# Sheet_V_3.net
KiCad netlist of a schematic drawn in Altium Designer
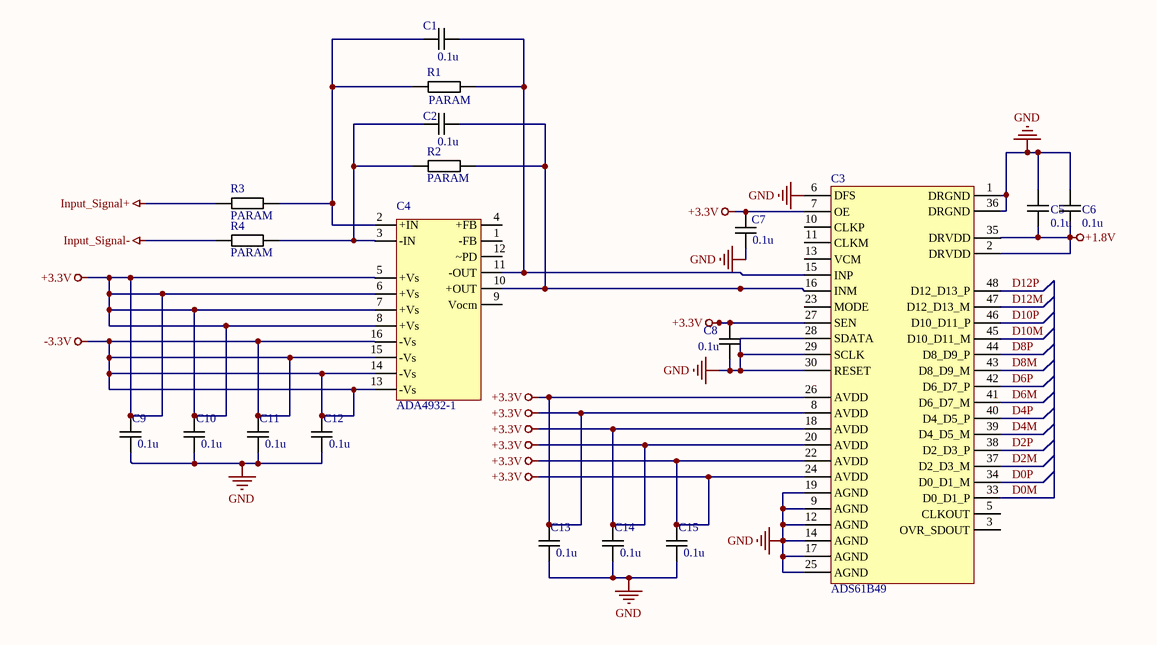
[diagram p0: Sheet_V№3.SchDoc]

(export (version "E")
  (design (tool "Eeschema 10.0.6"))
  (components
    (comp (ref "C1")
      (value "0.1u")
      (footprint "Capacitor")
      (libsource (lib "Schematic_Library_V№6") (part "Capacitor"))
    )
    (comp (ref "C2")
      (value "0.1u")
      (footprint "Capacitor")
      (libsource (lib "Schematic_Library_V№6") (part "Capacitor"))
    )
    (comp (ref "C3")
      (value "ADS61B49")
      (footprint "ADS61B49")
      (libsource (lib "Schematic_library_V№3") (part "ADS61B49"))
    )
    (comp (ref "C4")
      (value "ADA4932-1")
      (footprint "PCB_Library_V№6:CP-16-2")
      (libsource (lib "Schematic_Library_V№6") (part "ADA4932-1"))
    )
    (comp (ref "C5")
      (value "0.1u")
      (footprint "Capacitor")
      (libsource (lib "Schematic_library_V№3") (part "Capacitor"))
    )
    (comp (ref "C6")
      (value "0.1u")
      (footprint "Capacitor")
      (libsource (lib "Schematic_library_V№3") (part "Capacitor"))
    )
    (comp (ref "C7")
      (value "0.1u")
      (footprint "Capacitor")
      (libsource (lib "Schematic_Library_V№6") (part "Capacitor"))
    )
    (comp (ref "C8")
      (value "0.1u")
      (footprint "Capacitor")
      (libsource (lib "Schematic_library_V№3") (part "Capacitor"))
    )
    (comp (ref "C9")
      (value "0.1u")
      (footprint "Capacitor")
      (libsource (lib "Schematic_Library_V№6") (part "Capacitor"))
    )
    (comp (ref "C10")
      (value "0.1u")
      (footprint "Capacitor")
      (libsource (lib "Schematic_Library_V№6") (part "Capacitor"))
    )
    (comp (ref "C11")
      (value "0.1u")
      (footprint "Capacitor")
      (libsource (lib "Schematic_Library_V№6") (part "Capacitor"))
    )
    (comp (ref "C12")
      (value "0.1u")
      (footprint "Capacitor")
      (libsource (lib "Schematic_Library_V№6") (part "Capacitor"))
    )
    (comp (ref "C13")
      (value "0.1u")
      (footprint "Capacitor")
      (libsource (lib "Schematic_Library_V№6") (part "Capacitor"))
    )
    (comp (ref "C14")
      (value "0.1u")
      (footprint "Capacitor")
      (libsource (lib "Schematic_Library_V№6") (part "Capacitor"))
    )
    (comp (ref "C15")
      (value "0.1u")
      (footprint "Capacitor")
      (libsource (lib "Schematic_Library_V№6") (part "Capacitor"))
    )
    (comp (ref "R1")
      (value "PARAM")
      (footprint "Resistor")
      (libsource (lib "Schematic_Library_V№6") (part "Resistor"))
    )
    (comp (ref "R2")
      (value "PARAM")
      (footprint "Resistor")
      (libsource (lib "Schematic_Library_V№6") (part "Resistor"))
    )
    (comp (ref "R3")
      (value "PARAM")
      (footprint "Resistor")
      (libsource (lib "Schematic_Library_V№6") (part "Resistor"))
    )
    (comp (ref "R4")
      (value "PARAM")
      (footprint "Resistor")
      (libsource (lib "Schematic_Library_V№6") (part "Resistor"))
    )
  )
  (nets
    (net (code "1") (name "+1.8V") (class "Default")
      (node (ref "C3") (pin "2") (pinfunction "DRVDD_2") (pintype "power_in"))
      (node (ref "C3") (pin "35") (pinfunction "DRVDD_35") (pintype "power_in"))
      (node (ref "C5") (pin "2") (pinfunction "2_2") (pintype "passive"))
      (node (ref "C6") (pin "2") (pinfunction "2_2") (pintype "passive"))
    )
    (net (code "2") (name "+3.3V") (class "Default")
      (node (ref "C10") (pin "2") (pinfunction "2_2") (pintype "passive"))
      (node (ref "C13") (pin "2") (pinfunction "2_2") (pintype "passive"))
      (node (ref "C14") (pin "2") (pinfunction "2_2") (pintype "passive"))
      (node (ref "C15") (pin "2") (pinfunction "2_2") (pintype "passive"))
      (node (ref "C3") (pin "18") (pinfunction "AVDD_18") (pintype "power_in"))
      (node (ref "C3") (pin "20") (pinfunction "AVDD_20") (pintype "power_in"))
      (node (ref "C3") (pin "22") (pinfunction "AVDD_22") (pintype "power_in"))
      (node (ref "C3") (pin "24") (pinfunction "AVDD_24") (pintype "power_in"))
      (node (ref "C3") (pin "26") (pinfunction "AVDD_26") (pintype "power_in"))
      (node (ref "C3") (pin "27") (pinfunction "SEN_27") (pintype "passive"))
      (node (ref "C3") (pin "7") (pinfunction "OE_7") (pintype "passive"))
      (node (ref "C3") (pin "8") (pinfunction "AVDD_8") (pintype "power_in"))
      (node (ref "C4") (pin "5") (pinfunction "+Vs_5") (pintype "passive"))
      (node (ref "C4") (pin "6") (pinfunction "+Vs_6") (pintype "passive"))
      (node (ref "C4") (pin "7") (pinfunction "+Vs_7") (pintype "passive"))
      (node (ref "C4") (pin "8") (pinfunction "+Vs_8") (pintype "passive"))
      (node (ref "C7") (pin "2") (pinfunction "2_2") (pintype "passive"))
      (node (ref "C8") (pin "2") (pinfunction "2_2") (pintype "passive"))
      (node (ref "C9") (pin "2") (pinfunction "2_2") (pintype "passive"))
    )
    (net (code "3") (name "-3.3V") (class "Default")
      (node (ref "C11") (pin "2") (pinfunction "2_2") (pintype "passive"))
      (node (ref "C12") (pin "2") (pinfunction "2_2") (pintype "passive"))
      (node (ref "C4") (pin "13") (pinfunction "-Vs_13") (pintype "passive"))
      (node (ref "C4") (pin "14") (pinfunction "-Vs_14") (pintype "passive"))
      (node (ref "C4") (pin "15") (pinfunction "-Vs_15") (pintype "passive"))
      (node (ref "C4") (pin "16") (pinfunction "-Vs_16") (pintype "passive"))
    )
    (net (code "4") (name "/D0M") (class "Default")
      (node (ref "C3") (pin "33") (pinfunction "D0_D1_P_33") (pintype "passive"))
    )
    (net (code "5") (name "/D0P") (class "Default")
      (node (ref "C3") (pin "34") (pinfunction "D0_D1_M_34") (pintype "passive"))
    )
    (net (code "6") (name "/D2M") (class "Default")
      (node (ref "C3") (pin "37") (pinfunction "D2_D3_M_37") (pintype "passive"))
    )
    (net (code "7") (name "/D2P") (class "Default")
      (node (ref "C3") (pin "38") (pinfunction "D2_D3_P_38") (pintype "passive"))
    )
    (net (code "8") (name "/D4M") (class "Default")
      (node (ref "C3") (pin "39") (pinfunction "D4_D5_M_39") (pintype "passive"))
    )
    (net (code "9") (name "/D4P") (class "Default")
      (node (ref "C3") (pin "40") (pinfunction "D4_D5_P_40") (pintype "passive"))
    )
    (net (code "10") (name "/D6M") (class "Default")
      (node (ref "C3") (pin "41") (pinfunction "D6_D7_M_41") (pintype "passive"))
    )
    (net (code "11") (name "/D6P") (class "Default")
      (node (ref "C3") (pin "42") (pinfunction "D6_D7_P_42") (pintype "passive"))
    )
    (net (code "12") (name "/D8M") (class "Default")
      (node (ref "C3") (pin "43") (pinfunction "D8_D9_M_43") (pintype "passive"))
    )
    (net (code "13") (name "/D8P") (class "Default")
      (node (ref "C3") (pin "44") (pinfunction "D8_D9_P_44") (pintype "passive"))
    )
    (net (code "14") (name "/D10M") (class "Default")
      (node (ref "C3") (pin "45") (pinfunction "D10_D11_M_45") (pintype "passive"))
    )
    (net (code "15") (name "/D10P") (class "Default")
      (node (ref "C3") (pin "46") (pinfunction "D10_D11_P_46") (pintype "passive"))
    )
    (net (code "16") (name "/D12M") (class "Default")
      (node (ref "C3") (pin "47") (pinfunction "D12_D13_M_47") (pintype "passive"))
    )
    (net (code "17") (name "/D12P") (class "Default")
      (node (ref "C3") (pin "48") (pinfunction "D12_D13_P_48") (pintype "passive"))
    )
    (net (code "18") (name "GND") (class "Default")
      (node (ref "C10") (pin "1") (pinfunction "1_1") (pintype "passive"))
      (node (ref "C11") (pin "1") (pinfunction "1_1") (pintype "passive"))
      (node (ref "C12") (pin "1") (pinfunction "1_1") (pintype "passive"))
      (node (ref "C13") (pin "1") (pinfunction "1_1") (pintype "passive"))
      (node (ref "C14") (pin "1") (pinfunction "1_1") (pintype "passive"))
      (node (ref "C15") (pin "1") (pinfunction "1_1") (pintype "passive"))
      (node (ref "C3") (pin "1") (pinfunction "DRGND_1") (pintype "power_in"))
      (node (ref "C3") (pin "12") (pinfunction "AGND_12") (pintype "power_in"))
      (node (ref "C3") (pin "14") (pinfunction "AGND_14") (pintype "power_in"))
      (node (ref "C3") (pin "17") (pinfunction "AGND_17") (pintype "power_in"))
      (node (ref "C3") (pin "19") (pinfunction "AGND_19") (pintype "power_in"))
      (node (ref "C3") (pin "25") (pinfunction "AGND_25") (pintype "power_in"))
      (node (ref "C3") (pin "28") (pinfunction "SDATA_28") (pintype "passive"))
      (node (ref "C3") (pin "29") (pinfunction "SCLK_29") (pintype "passive"))
      (node (ref "C3") (pin "30") (pinfunction "RESET_30") (pintype "passive"))
      (node (ref "C3") (pin "36") (pinfunction "DRGND_36") (pintype "power_in"))
      (node (ref "C3") (pin "6") (pinfunction "DFS_6") (pintype "passive"))
      (node (ref "C3") (pin "9") (pinfunction "AGND_9") (pintype "power_in"))
      (node (ref "C5") (pin "1") (pinfunction "1_1") (pintype "passive"))
      (node (ref "C6") (pin "1") (pinfunction "1_1") (pintype "passive"))
      (node (ref "C7") (pin "1") (pinfunction "1_1") (pintype "passive"))
      (node (ref "C8") (pin "1") (pinfunction "1_1") (pintype "passive"))
      (node (ref "C9") (pin "1") (pinfunction "1_1") (pintype "passive"))
    )
    (net (code "19") (name "Input_Signal+") (class "Default")
      (node (ref "R3") (pin "1") (pinfunction "1_1") (pintype "passive"))
    )
    (net (code "20") (name "Input_Signal-") (class "Default")
      (node (ref "R4") (pin "1") (pinfunction "1_1") (pintype "passive"))
    )
    (net (code "21") (name "Net-(C3-INM)") (class "Default")
      (node (ref "C2") (pin "2") (pinfunction "2_2") (pintype "passive"))
      (node (ref "C3") (pin "16") (pinfunction "INM_16") (pintype "passive"))
      (node (ref "C4") (pin "10") (pinfunction "+OUT_10") (pintype "passive"))
      (node (ref "R2") (pin "2") (pinfunction "2_2") (pintype "passive"))
    )
    (net (code "22") (name "Net-(C3-INP)") (class "Default")
      (node (ref "C1") (pin "1") (pinfunction "1_1") (pintype "passive"))
      (node (ref "C3") (pin "15") (pinfunction "INP_15") (pintype "passive"))
      (node (ref "C4") (pin "11") (pinfunction "-OUT_11") (pintype "passive"))
      (node (ref "R1") (pin "2") (pinfunction "2_2") (pintype "passive"))
    )
    (net (code "23") (name "Net-(C4-+IN)") (class "Default")
      (node (ref "C1") (pin "2") (pinfunction "2_2") (pintype "passive"))
      (node (ref "C4") (pin "2") (pinfunction "+IN_2") (pintype "passive"))
      (node (ref "R1") (pin "1") (pinfunction "1_1") (pintype "passive"))
      (node (ref "R3") (pin "2") (pinfunction "2_2") (pintype "passive"))
    )
    (net (code "24") (name "Net-(C4--IN)") (class "Default")
      (node (ref "C2") (pin "1") (pinfunction "1_1") (pintype "passive"))
      (node (ref "C4") (pin "3") (pinfunction "-IN_3") (pintype "passive"))
      (node (ref "R2") (pin "1") (pinfunction "1_1") (pintype "passive"))
      (node (ref "R4") (pin "2") (pinfunction "2_2") (pintype "passive"))
    )
    (net (code "25") (name "unconnected-(C3-CLKM-Pad11)") (class "Default")
      (node (ref "C3") (pin "11") (pinfunction "CLKM_11") (pintype "passive"))
    )
    (net (code "26") (name "unconnected-(C3-CLKOUT-Pad5)") (class "Default")
      (node (ref "C3") (pin "5") (pinfunction "CLKOUT_5") (pintype "passive"))
    )
    (net (code "27") (name "unconnected-(C3-CLKP-Pad10)") (class "Default")
      (node (ref "C3") (pin "10") (pinfunction "CLKP_10") (pintype "passive"))
    )
    (net (code "28") (name "unconnected-(C3-MODE-Pad23)") (class "Default")
      (node (ref "C3") (pin "23") (pinfunction "MODE_23") (pintype "passive"))
    )
    (net (code "29") (name "unconnected-(C3-OVR_SDOUT-Pad3)") (class "Default")
      (node (ref "C3") (pin "3") (pinfunction "OVR_SDOUT_3") (pintype "passive"))
    )
    (net (code "30") (name "unconnected-(C3-VCM-Pad13)") (class "Default")
      (node (ref "C3") (pin "13") (pinfunction "VCM_13") (pintype "passive"))
    )
    (net (code "31") (name "unconnected-(C4-+FB-Pad4)") (class "Default")
      (node (ref "C4") (pin "4") (pinfunction "+FB_4") (pintype "passive"))
    )
    (net (code "32") (name "unconnected-(C4--FB-Pad1)") (class "Default")
      (node (ref "C4") (pin "1") (pinfunction "-FB_1") (pintype "passive"))
    )
    (net (code "33") (name "unconnected-(C4-Vocm-Pad9)") (class "Default")
      (node (ref "C4") (pin "9") (pinfunction "Vocm_9") (pintype "passive"))
    )
    (net (code "34") (name "unconnected-(C4-~PD-Pad12)") (class "Default")
      (node (ref "C4") (pin "12") (pinfunction "~PD_12") (pintype "passive"))
    )
  )
)
